# level_bjt.net
KiCad netlist of a schematic drawn in EAGLE
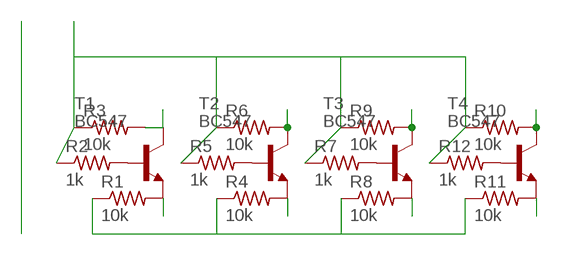
[diagram p0: schematic, sheet 1]

(export (version "E")
  (design (tool "Eeschema 10.0.6"))
  (components
    (comp (ref "R1")
      (value "10k")
      (footprint "eagle-import:0204_5")
      (libsource (lib "eagle-import") (part "R-US_0204/5"))
    )
    (comp (ref "R2")
      (value "1k")
      (footprint "eagle-import:0204_5")
      (libsource (lib "eagle-import") (part "R-US_0204/5"))
    )
    (comp (ref "R3")
      (value "10k")
      (footprint "eagle-import:0204_5")
      (libsource (lib "eagle-import") (part "R-US_0204/5"))
    )
    (comp (ref "R4")
      (value "10k")
      (footprint "eagle-import:0204_5")
      (libsource (lib "eagle-import") (part "R-US_0204/5"))
    )
    (comp (ref "R5")
      (value "1k")
      (footprint "eagle-import:0204_5")
      (libsource (lib "eagle-import") (part "R-US_0204/5"))
    )
    (comp (ref "R6")
      (value "10k")
      (footprint "eagle-import:0204_5")
      (libsource (lib "eagle-import") (part "R-US_0204/5"))
    )
    (comp (ref "R7")
      (value "1k")
      (footprint "eagle-import:0204_5")
      (libsource (lib "eagle-import") (part "R-US_0204/5"))
    )
    (comp (ref "R8")
      (value "10k")
      (footprint "eagle-import:0204_5")
      (libsource (lib "eagle-import") (part "R-US_0204/5"))
    )
    (comp (ref "R9")
      (value "10k")
      (footprint "eagle-import:0204_5")
      (libsource (lib "eagle-import") (part "R-US_0204/5"))
    )
    (comp (ref "R10")
      (value "10k")
      (footprint "eagle-import:0204_5")
      (libsource (lib "eagle-import") (part "R-US_0204/5"))
    )
    (comp (ref "R11")
      (value "10k")
      (footprint "eagle-import:0204_5")
      (libsource (lib "eagle-import") (part "R-US_0204/5"))
    )
    (comp (ref "R12")
      (value "1k")
      (footprint "eagle-import:0204_5")
      (libsource (lib "eagle-import") (part "R-US_0204/5"))
    )
    (comp (ref "T1")
      (value "BC547")
      (footprint "eagle-import:TO92")
      (libsource (lib "eagle-import") (part "BC547"))
    )
    (comp (ref "T2")
      (value "BC547")
      (footprint "eagle-import:TO92")
      (libsource (lib "eagle-import") (part "BC547"))
    )
    (comp (ref "T3")
      (value "BC547")
      (footprint "eagle-import:TO92")
      (libsource (lib "eagle-import") (part "BC547"))
    )
    (comp (ref "T4")
      (value "BC547")
      (footprint "eagle-import:TO92")
      (libsource (lib "eagle-import") (part "BC547"))
    )
  )
  (nets
    (net (code "1") (name "/N$3") (class "Default")
      (node (ref "R10") (pin "2") (pinfunction "2_2") (pintype "passive"))
      (node (ref "R6") (pin "2") (pinfunction "2_2") (pintype "passive"))
      (node (ref "R9") (pin "2") (pinfunction "2_2") (pintype "passive"))
      (node (ref "T2") (pin "3") (pinfunction "C_3") (pintype "passive"))
      (node (ref "T3") (pin "3") (pinfunction "C_3") (pintype "passive"))
      (node (ref "T4") (pin "3") (pinfunction "C_3") (pintype "passive"))
    )
    (net (code "2") (name "Net-(R1-Pad1)") (class "Default")
      (node (ref "R1") (pin "1") (pinfunction "1_1") (pintype "passive"))
      (node (ref "R11") (pin "1") (pinfunction "1_1") (pintype "passive"))
      (node (ref "R4") (pin "1") (pinfunction "1_1") (pintype "passive"))
      (node (ref "R8") (pin "1") (pinfunction "1_1") (pintype "passive"))
    )
    (net (code "3") (name "Net-(R10-Pad1)") (class "Default")
      (node (ref "R10") (pin "1") (pinfunction "1_1") (pintype "passive"))
      (node (ref "R12") (pin "1") (pinfunction "1_1") (pintype "passive"))
      (node (ref "R2") (pin "1") (pinfunction "1_1") (pintype "passive"))
      (node (ref "R3") (pin "1") (pinfunction "1_1") (pintype "passive"))
      (node (ref "R5") (pin "1") (pinfunction "1_1") (pintype "passive"))
      (node (ref "R6") (pin "1") (pinfunction "1_1") (pintype "passive"))
      (node (ref "R7") (pin "1") (pinfunction "1_1") (pintype "passive"))
      (node (ref "R9") (pin "1") (pinfunction "1_1") (pintype "passive"))
    )
    (net (code "4") (name "Net-(T1-B)") (class "Default")
      (node (ref "R2") (pin "2") (pinfunction "2_2") (pintype "passive"))
      (node (ref "T1") (pin "2") (pinfunction "B_2") (pintype "passive"))
    )
    (net (code "5") (name "Net-(T1-C)") (class "Default")
      (node (ref "R3") (pin "2") (pinfunction "2_2") (pintype "passive"))
      (node (ref "T1") (pin "3") (pinfunction "C_3") (pintype "passive"))
    )
    (net (code "6") (name "Net-(T1-E)") (class "Default")
      (node (ref "R1") (pin "2") (pinfunction "2_2") (pintype "passive"))
      (node (ref "T1") (pin "1") (pinfunction "E_1") (pintype "passive"))
    )
    (net (code "7") (name "Net-(T2-B)") (class "Default")
      (node (ref "R5") (pin "2") (pinfunction "2_2") (pintype "passive"))
      (node (ref "T2") (pin "2") (pinfunction "B_2") (pintype "passive"))
    )
    (net (code "8") (name "Net-(T2-E)") (class "Default")
      (node (ref "R4") (pin "2") (pinfunction "2_2") (pintype "passive"))
      (node (ref "T2") (pin "1") (pinfunction "E_1") (pintype "passive"))
    )
    (net (code "9") (name "Net-(T3-B)") (class "Default")
      (node (ref "R7") (pin "2") (pinfunction "2_2") (pintype "passive"))
      (node (ref "T3") (pin "2") (pinfunction "B_2") (pintype "passive"))
    )
    (net (code "10") (name "Net-(T3-E)") (class "Default")
      (node (ref "R8") (pin "2") (pinfunction "2_2") (pintype "passive"))
      (node (ref "T3") (pin "1") (pinfunction "E_1") (pintype "passive"))
    )
    (net (code "11") (name "Net-(T4-B)") (class "Default")
      (node (ref "R12") (pin "2") (pinfunction "2_2") (pintype "passive"))
      (node (ref "T4") (pin "2") (pinfunction "B_2") (pintype "passive"))
    )
    (net (code "12") (name "Net-(T4-E)") (class "Default")
      (node (ref "R11") (pin "2") (pinfunction "2_2") (pintype "passive"))
      (node (ref "T4") (pin "1") (pinfunction "E_1") (pintype "passive"))
    )
  )
)
